# greenscreamer.net
KiCad netlist of a schematic drawn in EAGLE
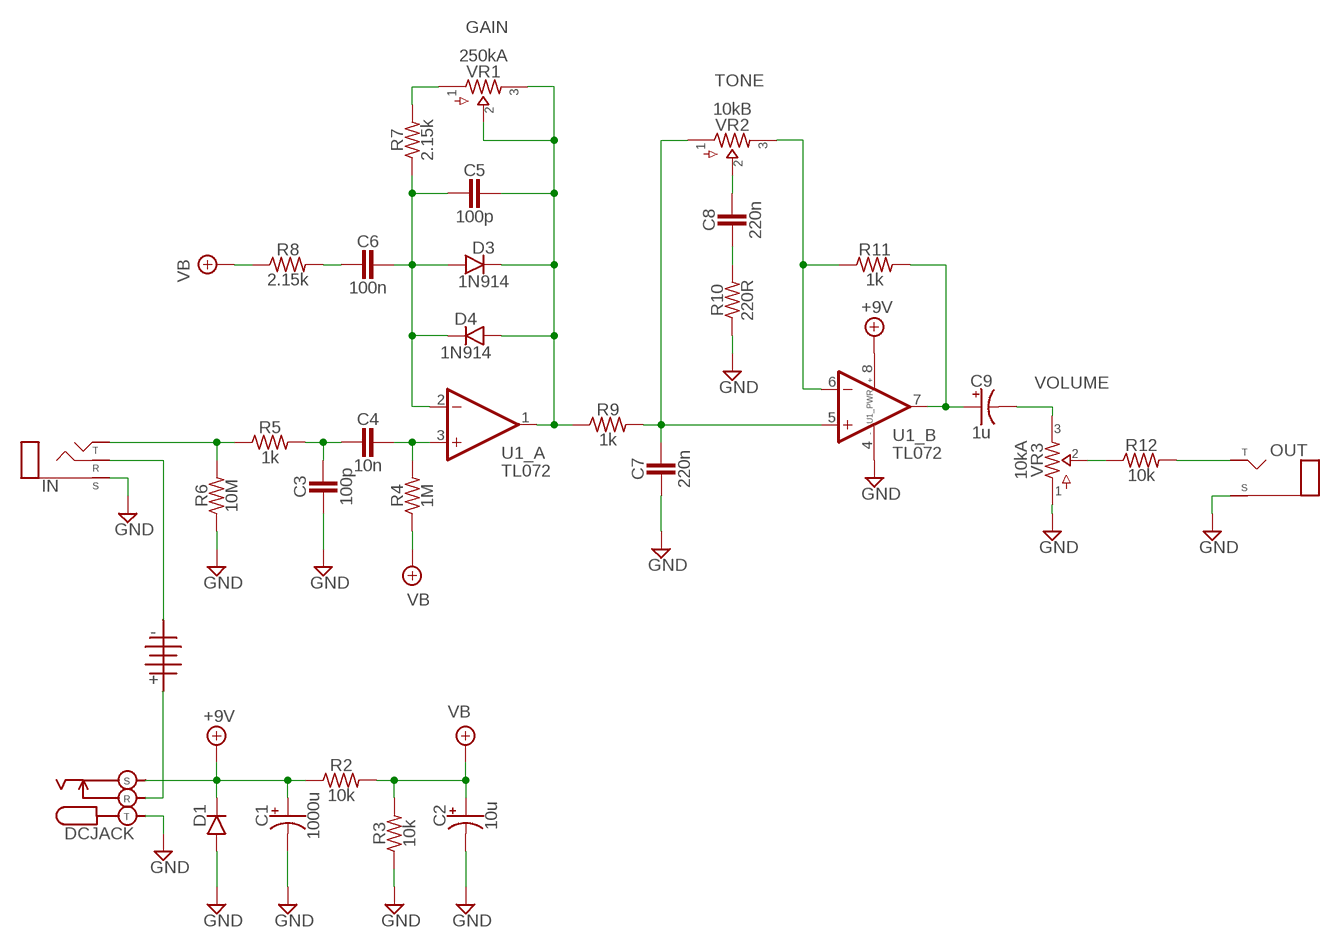
[diagram p0: schematic, sheet 1]

(export (version "E")
  (design (tool "Eeschema 10.0.6"))
  (components
    (comp (ref "1101")
      (value "BATTERY")
      (footprint "eagle-import:TWO_PADS")
      (libsource (lib "eagle-import") (part "BATTERY"))
    )
    (comp (ref "C1")
      (value "1000u")
      (footprint "eagle-import:050_020")
      (libsource (lib "eagle-import") (part "0500"))
    )
    (comp (ref "C2")
      (value "10u")
      (footprint "eagle-import:050_020")
      (libsource (lib "eagle-import") (part "0500"))
    )
    (comp (ref "C3")
      (value "100p")
      (footprint "eagle-import:BOX_SMALL")
      (libsource (lib "eagle-import") (part "CER/FILMBOX.1"))
    )
    (comp (ref "C4")
      (value "10n")
      (footprint "eagle-import:BOX_SMALL")
      (libsource (lib "eagle-import") (part "CER/FILMBOX.1"))
    )
    (comp (ref "C5")
      (value "100p")
      (footprint "eagle-import:BOX_SMALL")
      (libsource (lib "eagle-import") (part "CER/FILMBOX.1"))
    )
    (comp (ref "C6")
      (value "100n")
      (footprint "eagle-import:BOX_SMALL")
      (libsource (lib "eagle-import") (part "CER/FILMBOX.1"))
    )
    (comp (ref "C7")
      (value "220n")
      (footprint "eagle-import:BOX_SMALL")
      (libsource (lib "eagle-import") (part "CER/FILMBOX.1"))
    )
    (comp (ref "C8")
      (value "220n")
      (footprint "eagle-import:BOX_SMALL")
      (libsource (lib "eagle-import") (part "CER/FILMBOX.1"))
    )
    (comp (ref "C9")
      (value "1u")
      (footprint "eagle-import:050_020")
      (libsource (lib "eagle-import") (part "0500"))
    )
    (comp (ref "D1")
      (value "DO35.2")
      (footprint "eagle-import:DO35-2")
      (libsource (lib "eagle-import") (part "DO35.2"))
    )
    (comp (ref "D3")
      (value "1N914")
      (footprint "eagle-import:DO35-2")
      (libsource (lib "eagle-import") (part "DO35.2"))
    )
    (comp (ref "D4")
      (value "1N914")
      (footprint "eagle-import:DO35-2")
      (libsource (lib "eagle-import") (part "DO35.2"))
    )
    (comp (ref "DCJACK")
      (value "DCJACK")
      (footprint "eagle-import:DC_KOBICONN")
      (libsource (lib "eagle-import") (part "DC_KOBICONN"))
    )
    (comp (ref "IN")
      (value "STEREO3PADS")
      (footprint "eagle-import:THREEPADS")
      (libsource (lib "eagle-import") (part "STEREO3PADS"))
    )
    (comp (ref "OUT")
      (value "MONO")
      (footprint "eagle-import:TWO_PADS")
      (libsource (lib "eagle-import") (part "MONO"))
    )
    (comp (ref "R2")
      (value "10k")
      (footprint "eagle-import:R0207_3")
      (libsource (lib "eagle-import") (part "R_.3B"))
    )
    (comp (ref "R3")
      (value "10k")
      (footprint "eagle-import:R0207_3")
      (libsource (lib "eagle-import") (part "R_.3B"))
    )
    (comp (ref "R4")
      (value "1M")
      (footprint "eagle-import:R0207_3")
      (libsource (lib "eagle-import") (part "R_.3B"))
    )
    (comp (ref "R5")
      (value "1k")
      (footprint "eagle-import:R0207_3")
      (libsource (lib "eagle-import") (part "R_.3B"))
    )
    (comp (ref "R6")
      (value "10M")
      (footprint "eagle-import:R0207_3")
      (libsource (lib "eagle-import") (part "R_.3B"))
    )
    (comp (ref "R7")
      (value "2.15k")
      (footprint "eagle-import:R0207_3")
      (libsource (lib "eagle-import") (part "R_.3B"))
    )
    (comp (ref "R8")
      (value "2.15k")
      (footprint "eagle-import:R0207_3")
      (libsource (lib "eagle-import") (part "R_.3B"))
    )
    (comp (ref "R9")
      (value "1k")
      (footprint "eagle-import:R0207_3")
      (libsource (lib "eagle-import") (part "R_.3B"))
    )
    (comp (ref "R10")
      (value "220R")
      (footprint "eagle-import:R0207_3")
      (libsource (lib "eagle-import") (part "R_.3B"))
    )
    (comp (ref "R11")
      (value "1k")
      (footprint "eagle-import:R0207_3")
      (libsource (lib "eagle-import") (part "R_.3B"))
    )
    (comp (ref "R12")
      (value "10k")
      (footprint "eagle-import:R0207_3")
      (libsource (lib "eagle-import") (part "R_.3B"))
    )
    (comp (ref "U1")
      (value "TL072")
      (footprint "eagle-import:DIL0")
      (libsource (lib "eagle-import") (part "DUALTH"))
    )
    (comp (ref "VR1")
      (value "250kA")
      (footprint "eagle-import:16MM")
      (libsource (lib "eagle-import") (part "POTS16MM"))
    )
    (comp (ref "VR2")
      (value "10kB")
      (footprint "eagle-import:16MM")
      (libsource (lib "eagle-import") (part "POTS16MM"))
    )
    (comp (ref "VR3")
      (value "10kA")
      (footprint "eagle-import:16MM")
      (libsource (lib "eagle-import") (part "POTS16MM"))
    )
  )
  (nets
    (net (code "1") (name "+9V") (class "Default")
      (node (ref "C1") (pin "+") (pinfunction "+_+") (pintype "passive"))
      (node (ref "D1") (pin "C") (pinfunction "C_C") (pintype "passive"))
      (node (ref "DCJACK") (pin "S") (pinfunction "S_S") (pintype "bidirectional"))
      (node (ref "R2") (pin "1") (pinfunction "1_1") (pintype "passive"))
      (node (ref "U1") (pin "8") (pinfunction "V+_8") (pintype "power_in"))
    )
    (net (code "2") (name "GND") (class "Default")
      (node (ref "C1") (pin "-") (pinfunction "-_-") (pintype "passive"))
      (node (ref "C2") (pin "-") (pinfunction "-_-") (pintype "passive"))
      (node (ref "C3") (pin "2") (pinfunction "2_2") (pintype "passive"))
      (node (ref "C7") (pin "2") (pinfunction "2_2") (pintype "passive"))
      (node (ref "D1") (pin "A") (pinfunction "A_A") (pintype "passive"))
      (node (ref "DCJACK") (pin "T") (pinfunction "T_T") (pintype "bidirectional"))
      (node (ref "IN") (pin "SLEEVE") (pinfunction "S_SLEEVE") (pintype "passive"))
      (node (ref "OUT") (pin "S") (pinfunction "SLEEVE_S") (pintype "passive"))
      (node (ref "R10") (pin "1") (pinfunction "1_1") (pintype "passive"))
      (node (ref "R3") (pin "1") (pinfunction "1_1") (pintype "passive"))
      (node (ref "R6") (pin "1") (pinfunction "1_1") (pintype "passive"))
      (node (ref "U1") (pin "4") (pinfunction "V-_4") (pintype "power_in"))
      (node (ref "VR3") (pin "1") (pinfunction "1_1") (pintype "passive"))
    )
    (net (code "3") (name "Net-(1101-P$1)") (class "Default")
      (node (ref "1101") (pin "T") (pinfunction "P$1_T") (pintype "bidirectional"))
      (node (ref "DCJACK") (pin "R") (pinfunction "R_R") (pintype "bidirectional"))
    )
    (net (code "4") (name "Net-(1101-P$2)") (class "Default")
      (node (ref "1101") (pin "S") (pinfunction "P$2_S") (pintype "bidirectional"))
      (node (ref "IN") (pin "RING") (pinfunction "R_RING") (pintype "passive"))
    )
    (net (code "5") (name "Net-(C3-Pad1)") (class "Default")
      (node (ref "C3") (pin "1") (pinfunction "1_1") (pintype "passive"))
      (node (ref "C4") (pin "2") (pinfunction "2_2") (pintype "passive"))
      (node (ref "R5") (pin "2") (pinfunction "2_2") (pintype "passive"))
    )
    (net (code "6") (name "Net-(C6-Pad2)") (class "Default")
      (node (ref "C6") (pin "2") (pinfunction "2_2") (pintype "passive"))
      (node (ref "R8") (pin "2") (pinfunction "2_2") (pintype "passive"))
    )
    (net (code "7") (name "Net-(C8-Pad1)") (class "Default")
      (node (ref "C8") (pin "1") (pinfunction "1_1") (pintype "passive"))
      (node (ref "VR2") (pin "2") (pinfunction "2_2") (pintype "passive"))
    )
    (net (code "8") (name "Net-(C8-Pad2)") (class "Default")
      (node (ref "C8") (pin "2") (pinfunction "2_2") (pintype "passive"))
      (node (ref "R10") (pin "2") (pinfunction "2_2") (pintype "passive"))
    )
    (net (code "9") (name "Net-(C9-Pad-)") (class "Default")
      (node (ref "C9") (pin "-") (pinfunction "-_-") (pintype "passive"))
      (node (ref "VR3") (pin "3") (pinfunction "3_3") (pintype "passive"))
    )
    (net (code "10") (name "Net-(IN-T)") (class "Default")
      (node (ref "IN") (pin "TIP") (pinfunction "T_TIP") (pintype "passive"))
      (node (ref "R5") (pin "1") (pinfunction "1_1") (pintype "passive"))
      (node (ref "R6") (pin "2") (pinfunction "2_2") (pintype "passive"))
    )
    (net (code "11") (name "Net-(OUT-TIP)") (class "Default")
      (node (ref "OUT") (pin "T") (pinfunction "TIP_T") (pintype "passive"))
      (node (ref "R12") (pin "2") (pinfunction "2_2") (pintype "passive"))
    )
    (net (code "12") (name "Net-(R7-Pad2)") (class "Default")
      (node (ref "R7") (pin "2") (pinfunction "2_2") (pintype "passive"))
      (node (ref "VR1") (pin "1") (pinfunction "1_1") (pintype "passive"))
    )
    (net (code "13") (name "Net-(R12-Pad1)") (class "Default")
      (node (ref "R12") (pin "1") (pinfunction "1_1") (pintype "passive"))
      (node (ref "VR3") (pin "2") (pinfunction "2_2") (pintype "passive"))
    )
    (net (code "14") (name "Net-(U1A-+IN)") (class "Default")
      (node (ref "C4") (pin "1") (pinfunction "1_1") (pintype "passive"))
      (node (ref "R4") (pin "2") (pinfunction "2_2") (pintype "passive"))
      (node (ref "U1") (pin "3") (pinfunction "+IN_3") (pintype "input"))
    )
    (net (code "15") (name "Net-(U1A--IN)") (class "Default")
      (node (ref "C5") (pin "2") (pinfunction "2_2") (pintype "passive"))
      (node (ref "C6") (pin "1") (pinfunction "1_1") (pintype "passive"))
      (node (ref "D3") (pin "A") (pinfunction "A_A") (pintype "passive"))
      (node (ref "D4") (pin "C") (pinfunction "C_C") (pintype "passive"))
      (node (ref "R7") (pin "1") (pinfunction "1_1") (pintype "passive"))
      (node (ref "U1") (pin "2") (pinfunction "-IN_2") (pintype "input"))
    )
    (net (code "16") (name "Net-(U1A-OUT)") (class "Default")
      (node (ref "C5") (pin "1") (pinfunction "1_1") (pintype "passive"))
      (node (ref "D3") (pin "C") (pinfunction "C_C") (pintype "passive"))
      (node (ref "D4") (pin "A") (pinfunction "A_A") (pintype "passive"))
      (node (ref "R9") (pin "1") (pinfunction "1_1") (pintype "passive"))
      (node (ref "U1") (pin "1") (pinfunction "OUT_1") (pintype "output"))
      (node (ref "VR1") (pin "2") (pinfunction "2_2") (pintype "passive"))
      (node (ref "VR1") (pin "3") (pinfunction "3_3") (pintype "passive"))
    )
    (net (code "17") (name "Net-(U1B-+IN)") (class "Default")
      (node (ref "C7") (pin "1") (pinfunction "1_1") (pintype "passive"))
      (node (ref "R9") (pin "2") (pinfunction "2_2") (pintype "passive"))
      (node (ref "U1") (pin "5") (pinfunction "+IN_5") (pintype "input"))
      (node (ref "VR2") (pin "1") (pinfunction "1_1") (pintype "passive"))
    )
    (net (code "18") (name "Net-(U1B--IN)") (class "Default")
      (node (ref "R11") (pin "1") (pinfunction "1_1") (pintype "passive"))
      (node (ref "U1") (pin "6") (pinfunction "-IN_6") (pintype "input"))
      (node (ref "VR2") (pin "3") (pinfunction "3_3") (pintype "passive"))
    )
    (net (code "19") (name "Net-(U1B-OUT)") (class "Default")
      (node (ref "C9") (pin "+") (pinfunction "+_+") (pintype "passive"))
      (node (ref "R11") (pin "2") (pinfunction "2_2") (pintype "passive"))
      (node (ref "U1") (pin "7") (pinfunction "OUT_7") (pintype "output"))
    )
    (net (code "20") (name "VB") (class "Default")
      (node (ref "C2") (pin "+") (pinfunction "+_+") (pintype "passive"))
      (node (ref "R2") (pin "2") (pinfunction "2_2") (pintype "passive"))
      (node (ref "R3") (pin "2") (pinfunction "2_2") (pintype "passive"))
      (node (ref "R4") (pin "1") (pinfunction "1_1") (pintype "passive"))
      (node (ref "R8") (pin "1") (pinfunction "1_1") (pintype "passive"))
    )
  )
)
